# main.net
KiCad netlist of a schematic drawn in EAGLE
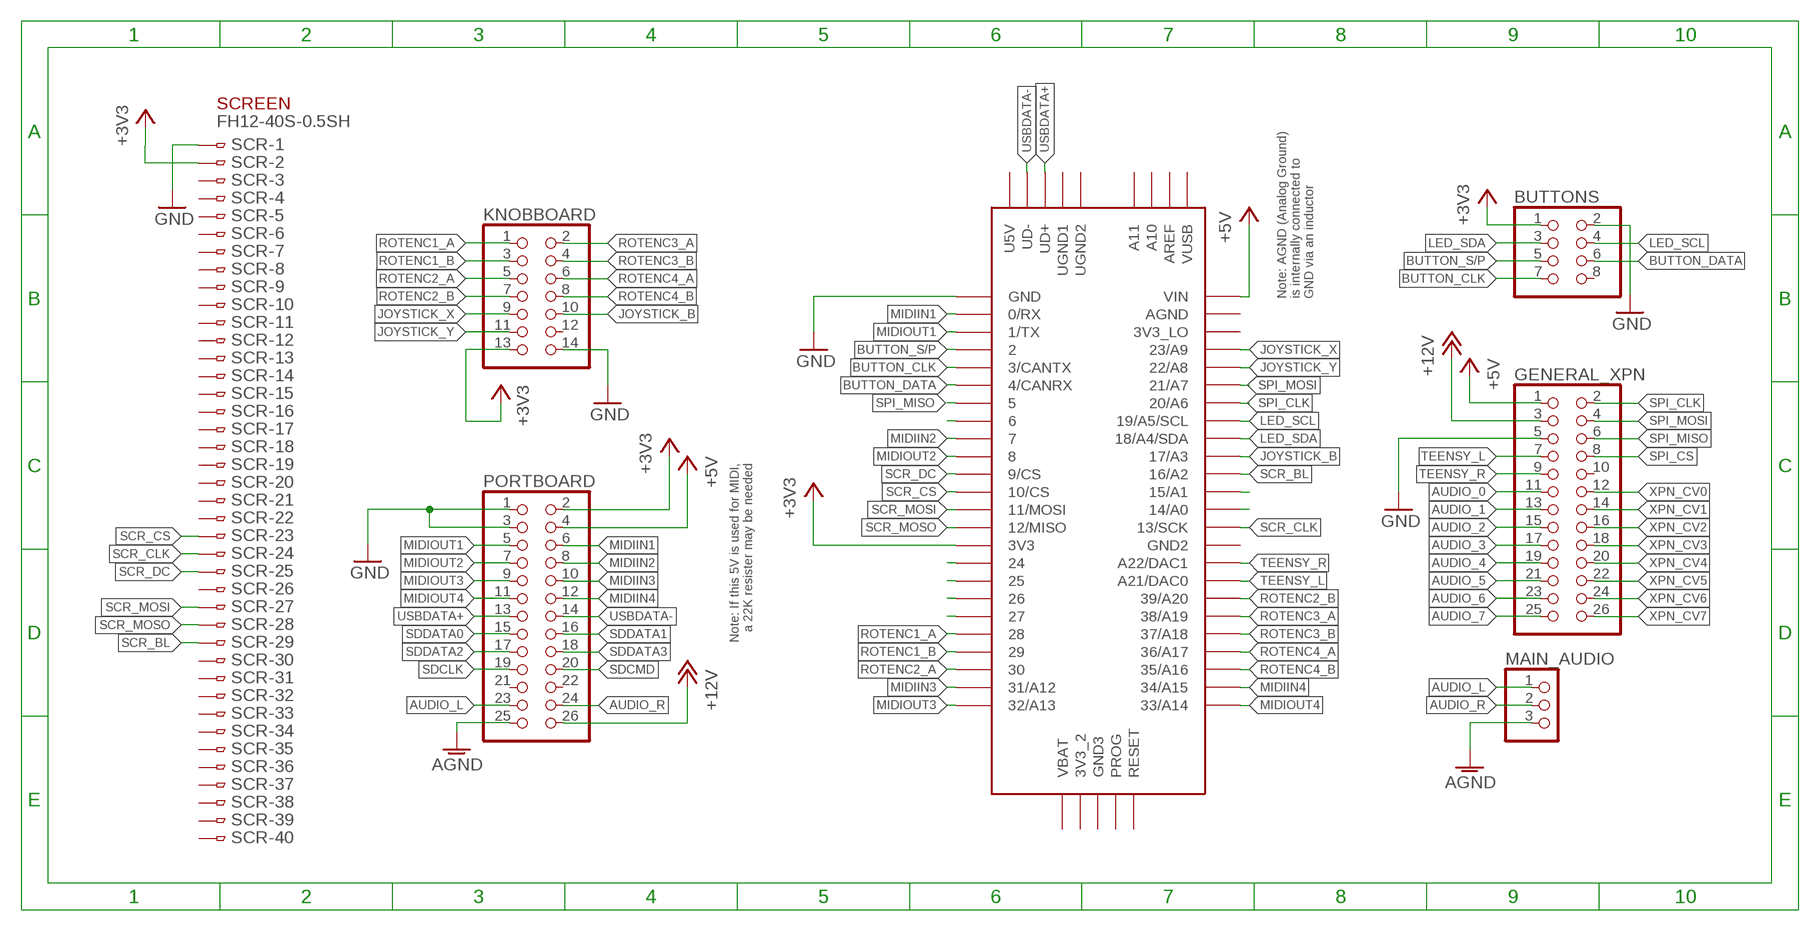
[diagram p0: schematic, sheet 1]

(export (version "E")
  (design (tool "Eeschema 10.0.6"))
  (components
    (comp (ref "BUTTONS")
      (value "PINHD-2X4")
      (footprint "eagle-import:2X04")
      (libsource (lib "eagle-import") (part "PINHD-2X4"))
    )
    (comp (ref "GENERAL_XPN")
      (value "PINHD-2X13")
      (footprint "eagle-import:2X13")
      (libsource (lib "eagle-import") (part "PINHD-2X13"))
    )
    (comp (ref "KNOBBOARD")
      (value "PINHD-2X7")
      (footprint "eagle-import:2X07")
      (libsource (lib "eagle-import") (part "PINHD-2X7"))
    )
    (comp (ref "MAIN_AUDIO")
      (value "PINHD-1X3")
      (footprint "eagle-import:1X03")
      (libsource (lib "eagle-import") (part "PINHD-1X3"))
    )
    (comp (ref "PORTBOARD")
      (value "PINHD-2X13")
      (footprint "eagle-import:2X13")
      (libsource (lib "eagle-import") (part "PINHD-2X13"))
    )
    (comp (ref "SCR")
      (value "FH12-40S-0.5SH")
      (footprint "eagle-import:FH12-40S-0.5SH")
      (fields (field (name "MPN") "FH12-40S-0.5SH(55)"))
      (libsource (lib "eagle-import") (part "FH12-40S-0.5SH"))
    )
    (comp (ref "TEENSY_3.6")
      (value "TEENSY_3.5/3.6")
      (footprint "eagle-import:TEENSY_3.5_3.6")
      (libsource (lib "eagle-import") (part "TEENSY_3.5/3.6"))
    )
  )
  (nets
    (net (code "1") (name "+3V3") (class "Default")
      (node (ref "BUTTONS") (pin "1") (pinfunction "1_1") (pintype "passive"))
      (node (ref "KNOBBOARD") (pin "13") (pinfunction "13_13") (pintype "passive"))
      (node (ref "PORTBOARD") (pin "2") (pinfunction "2_2") (pintype "passive"))
      (node (ref "SCR") (pin "2") (pinfunction "1_2") (pintype "passive"))
      (node (ref "TEENSY_3.6") (pin "3V3") (pinfunction "3V3_3V3") (pintype "bidirectional"))
    )
    (net (code "2") (name "+5V") (class "Default")
      (node (ref "GENERAL_XPN") (pin "1") (pinfunction "1_1") (pintype "passive"))
      (node (ref "PORTBOARD") (pin "4") (pinfunction "4_4") (pintype "passive"))
      (node (ref "TEENSY_3.6") (pin "VIN") (pinfunction "VIN_VIN") (pintype "bidirectional"))
    )
    (net (code "3") (name "+12V") (class "Default")
      (node (ref "GENERAL_XPN") (pin "3") (pinfunction "3_3") (pintype "passive"))
      (node (ref "PORTBOARD") (pin "26") (pinfunction "26_26") (pintype "passive"))
    )
    (net (code "4") (name "AGND") (class "Default")
      (node (ref "MAIN_AUDIO") (pin "3") (pinfunction "3_3") (pintype "passive"))
      (node (ref "PORTBOARD") (pin "25") (pinfunction "25_25") (pintype "passive"))
    )
    (net (code "5") (name "AUDIO_0") (class "Default")
      (node (ref "GENERAL_XPN") (pin "11") (pinfunction "11_11") (pintype "passive"))
    )
    (net (code "6") (name "AUDIO_1") (class "Default")
      (node (ref "GENERAL_XPN") (pin "13") (pinfunction "13_13") (pintype "passive"))
    )
    (net (code "7") (name "AUDIO_2") (class "Default")
      (node (ref "GENERAL_XPN") (pin "15") (pinfunction "15_15") (pintype "passive"))
    )
    (net (code "8") (name "AUDIO_3") (class "Default")
      (node (ref "GENERAL_XPN") (pin "17") (pinfunction "17_17") (pintype "passive"))
    )
    (net (code "9") (name "AUDIO_4") (class "Default")
      (node (ref "GENERAL_XPN") (pin "19") (pinfunction "19_19") (pintype "passive"))
    )
    (net (code "10") (name "AUDIO_5") (class "Default")
      (node (ref "GENERAL_XPN") (pin "21") (pinfunction "21_21") (pintype "passive"))
    )
    (net (code "11") (name "AUDIO_6") (class "Default")
      (node (ref "GENERAL_XPN") (pin "23") (pinfunction "23_23") (pintype "passive"))
    )
    (net (code "12") (name "AUDIO_7") (class "Default")
      (node (ref "GENERAL_XPN") (pin "25") (pinfunction "25_25") (pintype "passive"))
    )
    (net (code "13") (name "AUDIO_L") (class "Default")
      (node (ref "MAIN_AUDIO") (pin "1") (pinfunction "1_1") (pintype "passive"))
      (node (ref "PORTBOARD") (pin "23") (pinfunction "23_23") (pintype "passive"))
    )
    (net (code "14") (name "AUDIO_R") (class "Default")
      (node (ref "MAIN_AUDIO") (pin "2") (pinfunction "2_2") (pintype "passive"))
      (node (ref "PORTBOARD") (pin "24") (pinfunction "24_24") (pintype "passive"))
    )
    (net (code "15") (name "BUTTON_CLK") (class "Default")
      (node (ref "BUTTONS") (pin "7") (pinfunction "7_7") (pintype "passive"))
      (node (ref "TEENSY_3.6") (pin "3/CANTX") (pinfunction "3/CANTX_3/CANTX") (pintype "bidirectional"))
    )
    (net (code "16") (name "BUTTON_DATA") (class "Default")
      (node (ref "BUTTONS") (pin "6") (pinfunction "6_6") (pintype "passive"))
      (node (ref "TEENSY_3.6") (pin "4/CANRX") (pinfunction "4/CANRX_4/CANRX") (pintype "bidirectional"))
    )
    (net (code "17") (name "BUTTON_S{slash}P") (class "Default")
      (node (ref "BUTTONS") (pin "5") (pinfunction "5_5") (pintype "passive"))
      (node (ref "TEENSY_3.6") (pin "2") (pinfunction "2_2") (pintype "bidirectional"))
    )
    (net (code "18") (name "GND") (class "Default")
      (node (ref "BUTTONS") (pin "2") (pinfunction "2_2") (pintype "passive"))
      (node (ref "GENERAL_XPN") (pin "5") (pinfunction "5_5") (pintype "passive"))
      (node (ref "KNOBBOARD") (pin "14") (pinfunction "14_14") (pintype "passive"))
      (node (ref "PORTBOARD") (pin "1") (pinfunction "1_1") (pintype "passive"))
      (node (ref "PORTBOARD") (pin "3") (pinfunction "3_3") (pintype "passive"))
      (node (ref "SCR") (pin "1") (pinfunction "1_1") (pintype "passive"))
      (node (ref "TEENSY_3.6") (pin "GND") (pinfunction "GND_GND") (pintype "bidirectional"))
    )
    (net (code "19") (name "JOYSTICK_B") (class "Default")
      (node (ref "KNOBBOARD") (pin "10") (pinfunction "10_10") (pintype "passive"))
      (node (ref "TEENSY_3.6") (pin "17/A3") (pinfunction "17/A3_17/A3") (pintype "bidirectional"))
    )
    (net (code "20") (name "JOYSTICK_X") (class "Default")
      (node (ref "KNOBBOARD") (pin "9") (pinfunction "9_9") (pintype "passive"))
      (node (ref "TEENSY_3.6") (pin "23/A9") (pinfunction "23/A9_23/A9") (pintype "bidirectional"))
    )
    (net (code "21") (name "JOYSTICK_Y") (class "Default")
      (node (ref "KNOBBOARD") (pin "11") (pinfunction "11_11") (pintype "passive"))
      (node (ref "TEENSY_3.6") (pin "22/A8") (pinfunction "22/A8_22/A8") (pintype "bidirectional"))
    )
    (net (code "22") (name "LED_SCL") (class "Default")
      (node (ref "BUTTONS") (pin "4") (pinfunction "4_4") (pintype "passive"))
      (node (ref "TEENSY_3.6") (pin "19/A5/SCL") (pinfunction "19/A5/SCL_19/A5/SCL") (pintype "bidirectional"))
    )
    (net (code "23") (name "LED_SDA") (class "Default")
      (node (ref "BUTTONS") (pin "3") (pinfunction "3_3") (pintype "passive"))
      (node (ref "TEENSY_3.6") (pin "18/A4/SDA") (pinfunction "18/A4/SDA_18/A4/SDA") (pintype "bidirectional"))
    )
    (net (code "24") (name "MIDIIN1") (class "Default")
      (node (ref "PORTBOARD") (pin "6") (pinfunction "6_6") (pintype "passive"))
      (node (ref "TEENSY_3.6") (pin "0/RX") (pinfunction "0/RX_0/RX") (pintype "bidirectional"))
    )
    (net (code "25") (name "MIDIIN2") (class "Default")
      (node (ref "PORTBOARD") (pin "8") (pinfunction "8_8") (pintype "passive"))
      (node (ref "TEENSY_3.6") (pin "7") (pinfunction "7_7") (pintype "bidirectional"))
    )
    (net (code "26") (name "MIDIIN3") (class "Default")
      (node (ref "PORTBOARD") (pin "10") (pinfunction "10_10") (pintype "passive"))
      (node (ref "TEENSY_3.6") (pin "31/A12") (pinfunction "31/A12_31/A12") (pintype "bidirectional"))
    )
    (net (code "27") (name "MIDIIN4") (class "Default")
      (node (ref "PORTBOARD") (pin "12") (pinfunction "12_12") (pintype "passive"))
      (node (ref "TEENSY_3.6") (pin "34/A15") (pinfunction "34/A15_34/A15") (pintype "bidirectional"))
    )
    (net (code "28") (name "MIDIOUT1") (class "Default")
      (node (ref "PORTBOARD") (pin "5") (pinfunction "5_5") (pintype "passive"))
      (node (ref "TEENSY_3.6") (pin "1/TX") (pinfunction "1/TX_1/TX") (pintype "bidirectional"))
    )
    (net (code "29") (name "MIDIOUT2") (class "Default")
      (node (ref "PORTBOARD") (pin "7") (pinfunction "7_7") (pintype "passive"))
      (node (ref "TEENSY_3.6") (pin "8") (pinfunction "8_8") (pintype "bidirectional"))
    )
    (net (code "30") (name "MIDIOUT3") (class "Default")
      (node (ref "PORTBOARD") (pin "9") (pinfunction "9_9") (pintype "passive"))
      (node (ref "TEENSY_3.6") (pin "32/A13") (pinfunction "32/A13_32/A13") (pintype "bidirectional"))
    )
    (net (code "31") (name "MIDIOUT4") (class "Default")
      (node (ref "PORTBOARD") (pin "11") (pinfunction "11_11") (pintype "passive"))
      (node (ref "TEENSY_3.6") (pin "33/A14") (pinfunction "33/A14_33/A14") (pintype "bidirectional"))
    )
    (net (code "32") (name "ROTENC1_A") (class "Default")
      (node (ref "KNOBBOARD") (pin "1") (pinfunction "1_1") (pintype "passive"))
      (node (ref "TEENSY_3.6") (pin "28") (pinfunction "28_28") (pintype "bidirectional"))
    )
    (net (code "33") (name "ROTENC1_B") (class "Default")
      (node (ref "KNOBBOARD") (pin "3") (pinfunction "3_3") (pintype "passive"))
      (node (ref "TEENSY_3.6") (pin "29") (pinfunction "29_29") (pintype "bidirectional"))
    )
    (net (code "34") (name "ROTENC2_A") (class "Default")
      (node (ref "KNOBBOARD") (pin "5") (pinfunction "5_5") (pintype "passive"))
      (node (ref "TEENSY_3.6") (pin "30") (pinfunction "30_30") (pintype "bidirectional"))
    )
    (net (code "35") (name "ROTENC2_B") (class "Default")
      (node (ref "KNOBBOARD") (pin "7") (pinfunction "7_7") (pintype "passive"))
      (node (ref "TEENSY_3.6") (pin "39/A20") (pinfunction "39/A20_39/A20") (pintype "bidirectional"))
    )
    (net (code "36") (name "ROTENC3_A") (class "Default")
      (node (ref "KNOBBOARD") (pin "2") (pinfunction "2_2") (pintype "passive"))
      (node (ref "TEENSY_3.6") (pin "38/A19") (pinfunction "38/A19_38/A19") (pintype "bidirectional"))
    )
    (net (code "37") (name "ROTENC3_B") (class "Default")
      (node (ref "KNOBBOARD") (pin "4") (pinfunction "4_4") (pintype "passive"))
      (node (ref "TEENSY_3.6") (pin "37/A18") (pinfunction "37/A18_37/A18") (pintype "bidirectional"))
    )
    (net (code "38") (name "ROTENC4_A") (class "Default")
      (node (ref "KNOBBOARD") (pin "6") (pinfunction "6_6") (pintype "passive"))
      (node (ref "TEENSY_3.6") (pin "36/A17") (pinfunction "36/A17_36/A17") (pintype "bidirectional"))
    )
    (net (code "39") (name "ROTENC4_B") (class "Default")
      (node (ref "KNOBBOARD") (pin "8") (pinfunction "8_8") (pintype "passive"))
      (node (ref "TEENSY_3.6") (pin "35/A16") (pinfunction "35/A16_35/A16") (pintype "bidirectional"))
    )
    (net (code "40") (name "SCR_BL") (class "Default")
      (node (ref "SCR") (pin "29") (pinfunction "1_29") (pintype "passive"))
      (node (ref "TEENSY_3.6") (pin "16/A2") (pinfunction "16/A2_16/A2") (pintype "bidirectional"))
    )
    (net (code "41") (name "SCR_CLK") (class "Default")
      (node (ref "SCR") (pin "24") (pinfunction "1_24") (pintype "passive"))
      (node (ref "TEENSY_3.6") (pin "13/SCK") (pinfunction "13/SCK_13/SCK") (pintype "bidirectional"))
    )
    (net (code "42") (name "SCR_CS") (class "Default")
      (node (ref "SCR") (pin "23") (pinfunction "1_23") (pintype "passive"))
      (node (ref "TEENSY_3.6") (pin "10/CS") (pinfunction "10/CS_10/CS") (pintype "bidirectional"))
    )
    (net (code "43") (name "SCR_DC") (class "Default")
      (node (ref "SCR") (pin "25") (pinfunction "1_25") (pintype "passive"))
      (node (ref "TEENSY_3.6") (pin "9/CS") (pinfunction "9/CS_9/CS") (pintype "bidirectional"))
    )
    (net (code "44") (name "SCR_MOSI") (class "Default")
      (node (ref "SCR") (pin "27") (pinfunction "1_27") (pintype "passive"))
      (node (ref "TEENSY_3.6") (pin "11/MOSI") (pinfunction "11/MOSI_11/MOSI") (pintype "bidirectional"))
    )
    (net (code "45") (name "SCR_MOSO") (class "Default")
      (node (ref "SCR") (pin "28") (pinfunction "1_28") (pintype "passive"))
      (node (ref "TEENSY_3.6") (pin "12/MISO") (pinfunction "12/MISO_12/MISO") (pintype "bidirectional"))
    )
    (net (code "46") (name "SDCLK") (class "Default")
      (node (ref "PORTBOARD") (pin "19") (pinfunction "19_19") (pintype "passive"))
    )
    (net (code "47") (name "SDCMD") (class "Default")
      (node (ref "PORTBOARD") (pin "20") (pinfunction "20_20") (pintype "passive"))
    )
    (net (code "48") (name "SDDATA0") (class "Default")
      (node (ref "PORTBOARD") (pin "15") (pinfunction "15_15") (pintype "passive"))
    )
    (net (code "49") (name "SDDATA1") (class "Default")
      (node (ref "PORTBOARD") (pin "16") (pinfunction "16_16") (pintype "passive"))
    )
    (net (code "50") (name "SDDATA2") (class "Default")
      (node (ref "PORTBOARD") (pin "17") (pinfunction "17_17") (pintype "passive"))
    )
    (net (code "51") (name "SDDATA3") (class "Default")
      (node (ref "PORTBOARD") (pin "18") (pinfunction "18_18") (pintype "passive"))
    )
    (net (code "52") (name "SPI_CLK") (class "Default")
      (node (ref "GENERAL_XPN") (pin "2") (pinfunction "2_2") (pintype "passive"))
      (node (ref "TEENSY_3.6") (pin "20/A6") (pinfunction "20/A6_20/A6") (pintype "bidirectional"))
    )
    (net (code "53") (name "SPI_CS") (class "Default")
      (node (ref "GENERAL_XPN") (pin "8") (pinfunction "8_8") (pintype "passive"))
    )
    (net (code "54") (name "SPI_MISO") (class "Default")
      (node (ref "GENERAL_XPN") (pin "6") (pinfunction "6_6") (pintype "passive"))
      (node (ref "TEENSY_3.6") (pin "5") (pinfunction "5_5") (pintype "bidirectional"))
    )
    (net (code "55") (name "SPI_MOSI") (class "Default")
      (node (ref "GENERAL_XPN") (pin "4") (pinfunction "4_4") (pintype "passive"))
      (node (ref "TEENSY_3.6") (pin "21/A7") (pinfunction "21/A7_21/A7") (pintype "bidirectional"))
    )
    (net (code "56") (name "TEENSY_L") (class "Default")
      (node (ref "GENERAL_XPN") (pin "7") (pinfunction "7_7") (pintype "passive"))
      (node (ref "TEENSY_3.6") (pin "21/DAC0") (pinfunction "A21/DAC0_21/DAC0") (pintype "bidirectional"))
    )
    (net (code "57") (name "TEENSY_R") (class "Default")
      (node (ref "GENERAL_XPN") (pin "9") (pinfunction "9_9") (pintype "passive"))
      (node (ref "TEENSY_3.6") (pin "A22/DAC1") (pinfunction "A22/DAC1_A22/DAC1") (pintype "bidirectional"))
    )
    (net (code "58") (name "USBDATA+") (class "Default")
      (node (ref "PORTBOARD") (pin "13") (pinfunction "13_13") (pintype "passive"))
      (node (ref "TEENSY_3.6") (pin "UD+") (pinfunction "UD+_UD+") (pintype "bidirectional"))
    )
    (net (code "59") (name "USBDATA-") (class "Default")
      (node (ref "PORTBOARD") (pin "14") (pinfunction "14_14") (pintype "passive"))
      (node (ref "TEENSY_3.6") (pin "UD-") (pinfunction "UD-_UD-") (pintype "bidirectional"))
    )
    (net (code "60") (name "XPN_CV0") (class "Default")
      (node (ref "GENERAL_XPN") (pin "12") (pinfunction "12_12") (pintype "passive"))
    )
    (net (code "61") (name "XPN_CV1") (class "Default")
      (node (ref "GENERAL_XPN") (pin "14") (pinfunction "14_14") (pintype "passive"))
    )
    (net (code "62") (name "XPN_CV2") (class "Default")
      (node (ref "GENERAL_XPN") (pin "16") (pinfunction "16_16") (pintype "passive"))
    )
    (net (code "63") (name "XPN_CV3") (class "Default")
      (node (ref "GENERAL_XPN") (pin "18") (pinfunction "18_18") (pintype "passive"))
    )
    (net (code "64") (name "XPN_CV4") (class "Default")
      (node (ref "GENERAL_XPN") (pin "20") (pinfunction "20_20") (pintype "passive"))
    )
    (net (code "65") (name "XPN_CV5") (class "Default")
      (node (ref "GENERAL_XPN") (pin "22") (pinfunction "22_22") (pintype "passive"))
    )
    (net (code "66") (name "XPN_CV6") (class "Default")
      (node (ref "GENERAL_XPN") (pin "24") (pinfunction "24_24") (pintype "passive"))
    )
    (net (code "67") (name "XPN_CV7") (class "Default")
      (node (ref "GENERAL_XPN") (pin "26") (pinfunction "26_26") (pintype "passive"))
    )
    (net (code "68") (name "unconnected-(BUTTONS-Pad8)") (class "Default")
      (node (ref "BUTTONS") (pin "8") (pinfunction "8_8") (pintype "passive"))
    )
    (net (code "69") (name "unconnected-(GENERAL_XPN-Pad10)") (class "Default")
      (node (ref "GENERAL_XPN") (pin "10") (pinfunction "10_10") (pintype "passive"))
    )
    (net (code "70") (name "unconnected-(KNOBBOARD-Pad12)") (class "Default")
      (node (ref "KNOBBOARD") (pin "12") (pinfunction "12_12") (pintype "passive"))
    )
    (net (code "71") (name "unconnected-(PORTBOARD-Pad21)") (class "Default")
      (node (ref "PORTBOARD") (pin "21") (pinfunction "21_21") (pintype "passive"))
    )
    (net (code "72") (name "unconnected-(PORTBOARD-Pad22)") (class "Default")
      (node (ref "PORTBOARD") (pin "22") (pinfunction "22_22") (pintype "passive"))
    )
    (net (code "73") (name "unconnected-(SCRAA-1-Pad33)") (class "Default")
      (node (ref "SCR") (pin "33") (pinfunction "1_33") (pintype "passive"))
    )
    (net (code "74") (name "unconnected-(SCRAB-1-Pad34)") (class "Default")
      (node (ref "SCR") (pin "34") (pinfunction "1_34") (pintype "passive"))
    )
    (net (code "75") (name "unconnected-(SCRAC-1-Pad35)") (class "Default")
      (node (ref "SCR") (pin "35") (pinfunction "1_35") (pintype "passive"))
    )
    (net (code "76") (name "unconnected-(SCRAD-1-Pad36)") (class "Default")
      (node (ref "SCR") (pin "36") (pinfunction "1_36") (pintype "passive"))
    )
    (net (code "77") (name "unconnected-(SCRAE-1-Pad37)") (class "Default")
      (node (ref "SCR") (pin "37") (pinfunction "1_37") (pintype "passive"))
    )
    (net (code "78") (name "unconnected-(SCRAF-1-Pad38)") (class "Default")
      (node (ref "SCR") (pin "38") (pinfunction "1_38") (pintype "passive"))
    )
    (net (code "79") (name "unconnected-(SCRAG-1-Pad39)") (class "Default")
      (node (ref "SCR") (pin "39") (pinfunction "1_39") (pintype "passive"))
    )
    (net (code "80") (name "unconnected-(SCRAH-1-Pad4)") (class "Default")
      (node (ref "SCR") (pin "4") (pinfunction "1_4") (pintype "passive"))
    )
    (net (code "81") (name "unconnected-(SCRAI-1-Pad40)") (class "Default")
      (node (ref "SCR") (pin "40") (pinfunction "1_40") (pintype "passive"))
    )
    (net (code "82") (name "unconnected-(SCRAJ-1-Pad5)") (class "Default")
      (node (ref "SCR") (pin "5") (pinfunction "1_5") (pintype "passive"))
    )
    (net (code "83") (name "unconnected-(SCRAK-1-Pad6)") (class "Default")
      (node (ref "SCR") (pin "6") (pinfunction "1_6") (pintype "passive"))
    )
    (net (code "84") (name "unconnected-(SCRAL-1-Pad7)") (class "Default")
      (node (ref "SCR") (pin "7") (pinfunction "1_7") (pintype "passive"))
    )
    (net (code "85") (name "unconnected-(SCRAM-1-Pad8)") (class "Default")
      (node (ref "SCR") (pin "8") (pinfunction "1_8") (pintype "passive"))
    )
    (net (code "86") (name "unconnected-(SCRAN-1-Pad9)") (class "Default")
      (node (ref "SCR") (pin "9") (pinfunction "1_9") (pintype "passive"))
    )
    (net (code "87") (name "unconnected-(SCRB-1-Pad10)") (class "Default")
      (node (ref "SCR") (pin "10") (pinfunction "1_10") (pintype "passive"))
    )
    (net (code "88") (name "unconnected-(SCRC-1-Pad11)") (class "Default")
      (node (ref "SCR") (pin "11") (pinfunction "1_11") (pintype "passive"))
    )
    (net (code "89") (name "unconnected-(SCRD-1-Pad12)") (class "Default")
      (node (ref "SCR") (pin "12") (pinfunction "1_12") (pintype "passive"))
    )
    (net (code "90") (name "unconnected-(SCRE-1-Pad13)") (class "Default")
      (node (ref "SCR") (pin "13") (pinfunction "1_13") (pintype "passive"))
    )
    (net (code "91") (name "unconnected-(SCRF-1-Pad14)") (class "Default")
      (node (ref "SCR") (pin "14") (pinfunction "1_14") (pintype "passive"))
    )
    (net (code "92") (name "unconnected-(SCRG-1-Pad15)") (class "Default")
      (node (ref "SCR") (pin "15") (pinfunction "1_15") (pintype "passive"))
    )
    (net (code "93") (name "unconnected-(SCRH-1-Pad16)") (class "Default")
      (node (ref "SCR") (pin "16") (pinfunction "1_16") (pintype "passive"))
    )
    (net (code "94") (name "unconnected-(SCRI-1-Pad17)") (class "Default")
      (node (ref "SCR") (pin "17") (pinfunction "1_17") (pintype "passive"))
    )
    (net (code "95") (name "unconnected-(SCRJ-1-Pad18)") (class "Default")
      (node (ref "SCR") (pin "18") (pinfunction "1_18") (pintype "passive"))
    )
    (net (code "96") (name "unconnected-(SCRK-1-Pad19)") (class "Default")
      (node (ref "SCR") (pin "19") (pinfunction "1_19") (pintype "passive"))
    )
    (net (code "97") (name "unconnected-(SCRM-1-Pad20)") (class "Default")
      (node (ref "SCR") (pin "20") (pinfunction "1_20") (pintype "passive"))
    )
    (net (code "98") (name "unconnected-(SCRN-1-Pad21)") (class "Default")
      (node (ref "SCR") (pin "21") (pinfunction "1_21") (pintype "passive"))
    )
    (net (code "99") (name "unconnected-(SCRO-1-Pad22)") (class "Default")
      (node (ref "SCR") (pin "22") (pinfunction "1_22") (pintype "passive"))
    )
    (net (code "100") (name "unconnected-(SCRS-1-Pad26)") (class "Default")
      (node (ref "SCR") (pin "26") (pinfunction "1_26") (pintype "passive"))
    )
    (net (code "101") (name "unconnected-(SCRW-1-Pad3)") (class "Default")
      (node (ref "SCR") (pin "3") (pinfunction "1_3") (pintype "passive"))
    )
    (net (code "102") (name "unconnected-(SCRX-1-Pad30)") (class "Default")
      (node (ref "SCR") (pin "30") (pinfunction "1_30") (pintype "passive"))
    )
    (net (code "103") (name "unconnected-(SCRY-1-Pad31)") (class "Default")
      (node (ref "SCR") (pin "31") (pinfunction "1_31") (pintype "passive"))
    )
    (net (code "104") (name "unconnected-(SCRZ-1-Pad32)") (class "Default")
      (node (ref "SCR") (pin "32") (pinfunction "1_32") (pintype "passive"))
    )
    (net (code "105") (name "unconnected-(TEENSY_3.6-Pad3V3_2)") (class "Default")
      (node (ref "TEENSY_3.6") (pin "3V3_2") (pinfunction "3V3_2_3V3_2") (pintype "bidirectional"))
    )
    (net (code "106") (name "unconnected-(TEENSY_3.6-Pad3V3_LO)") (class "Default")
      (node (ref "TEENSY_3.6") (pin "3V3_LO") (pinfunction "3V3_LO_3V3_LO") (pintype "bidirectional"))
    )
    (net (code "107") (name "unconnected-(TEENSY_3.6-Pad6)") (class "Default")
      (node (ref "TEENSY_3.6") (pin "6") (pinfunction "6_6") (pintype "bidirectional"))
    )
    (net (code "108") (name "unconnected-(TEENSY_3.6-Pad14{slash}A0)") (class "Default")
      (node (ref "TEENSY_3.6") (pin "14/A0") (pinfunction "14/A0_14/A0") (pintype "bidirectional"))
    )
    (net (code "109") (name "unconnected-(TEENSY_3.6-Pad15{slash}A1)") (class "Default")
      (node (ref "TEENSY_3.6") (pin "15/A1") (pinfunction "15/A1_15/A1") (pintype "bidirectional"))
    )
    (net (code "110") (name "unconnected-(TEENSY_3.6-Pad24)") (class "Default")
      (node (ref "TEENSY_3.6") (pin "24") (pinfunction "24_24") (pintype "bidirectional"))
    )
    (net (code "111") (name "unconnected-(TEENSY_3.6-Pad25)") (class "Default")
      (node (ref "TEENSY_3.6") (pin "25") (pinfunction "25_25") (pintype "bidirectional"))
    )
    (net (code "112") (name "unconnected-(TEENSY_3.6-Pad26)") (class "Default")
      (node (ref "TEENSY_3.6") (pin "26") (pinfunction "26_26") (pintype "bidirectional"))
    )
    (net (code "113") (name "unconnected-(TEENSY_3.6-Pad27)") (class "Default")
      (node (ref "TEENSY_3.6") (pin "27") (pinfunction "27_27") (pintype "bidirectional"))
    )
    (net (code "114") (name "unconnected-(TEENSY_3.6-PadA10)") (class "Default")
      (node (ref "TEENSY_3.6") (pin "A10") (pinfunction "A10_A10") (pintype "bidirectional"))
    )
    (net (code "115") (name "unconnected-(TEENSY_3.6-PadA11)") (class "Default")
      (node (ref "TEENSY_3.6") (pin "A11") (pinfunction "A11_A11") (pintype "bidirectional"))
    )
    (net (code "116") (name "unconnected-(TEENSY_3.6-PadAGND)") (class "Default")
      (node (ref "TEENSY_3.6") (pin "AGND") (pinfunction "AGND_AGND") (pintype "bidirectional"))
    )
    (net (code "117") (name "unconnected-(TEENSY_3.6-PadAREF)") (class "Default")
      (node (ref "TEENSY_3.6") (pin "AREF") (pinfunction "AREF_AREF") (pintype "bidirectional"))
    )
    (net (code "118") (name "unconnected-(TEENSY_3.6-PadGND2)") (class "Default")
      (node (ref "TEENSY_3.6") (pin "GND2") (pinfunction "GND2_GND2") (pintype "bidirectional"))
    )
    (net (code "119") (name "unconnected-(TEENSY_3.6-PadGND3)") (class "Default")
      (node (ref "TEENSY_3.6") (pin "GND3") (pinfunction "GND3_GND3") (pintype "bidirectional"))
    )
    (net (code "120") (name "unconnected-(TEENSY_3.6-PadPROG)") (class "Default")
      (node (ref "TEENSY_3.6") (pin "PROG") (pinfunction "PROG_PROG") (pintype "bidirectional"))
    )
    (net (code "121") (name "unconnected-(TEENSY_3.6-PadRESET)") (class "Default")
      (node (ref "TEENSY_3.6") (pin "RESET") (pinfunction "RESET_RESET") (pintype "bidirectional"))
    )
    (net (code "122") (name "unconnected-(TEENSY_3.6-PadU5V)") (class "Default")
      (node (ref "TEENSY_3.6") (pin "U5V") (pinfunction "U5V_U5V") (pintype "bidirectional"))
    )
    (net (code "123") (name "unconnected-(TEENSY_3.6-PadUGND1)") (class "Default")
      (node (ref "TEENSY_3.6") (pin "UGND1") (pinfunction "UGND1_UGND1") (pintype "bidirectional"))
    )
    (net (code "124") (name "unconnected-(TEENSY_3.6-PadUGND2)") (class "Default")
      (node (ref "TEENSY_3.6") (pin "UGND2") (pinfunction "UGND2_UGND2") (pintype "bidirectional"))
    )
    (net (code "125") (name "unconnected-(TEENSY_3.6-PadVBAT)") (class "Default")
      (node (ref "TEENSY_3.6") (pin "VBAT") (pinfunction "VBAT_VBAT") (pintype "bidirectional"))
    )
    (net (code "126") (name "unconnected-(TEENSY_3.6-PadVUSB)") (class "Default")
      (node (ref "TEENSY_3.6") (pin "VUSB") (pinfunction "VUSB_VUSB") (pintype "bidirectional"))
    )
  )
)
